# 609_motor.net
KiCad netlist of a schematic drawn in EAGLE
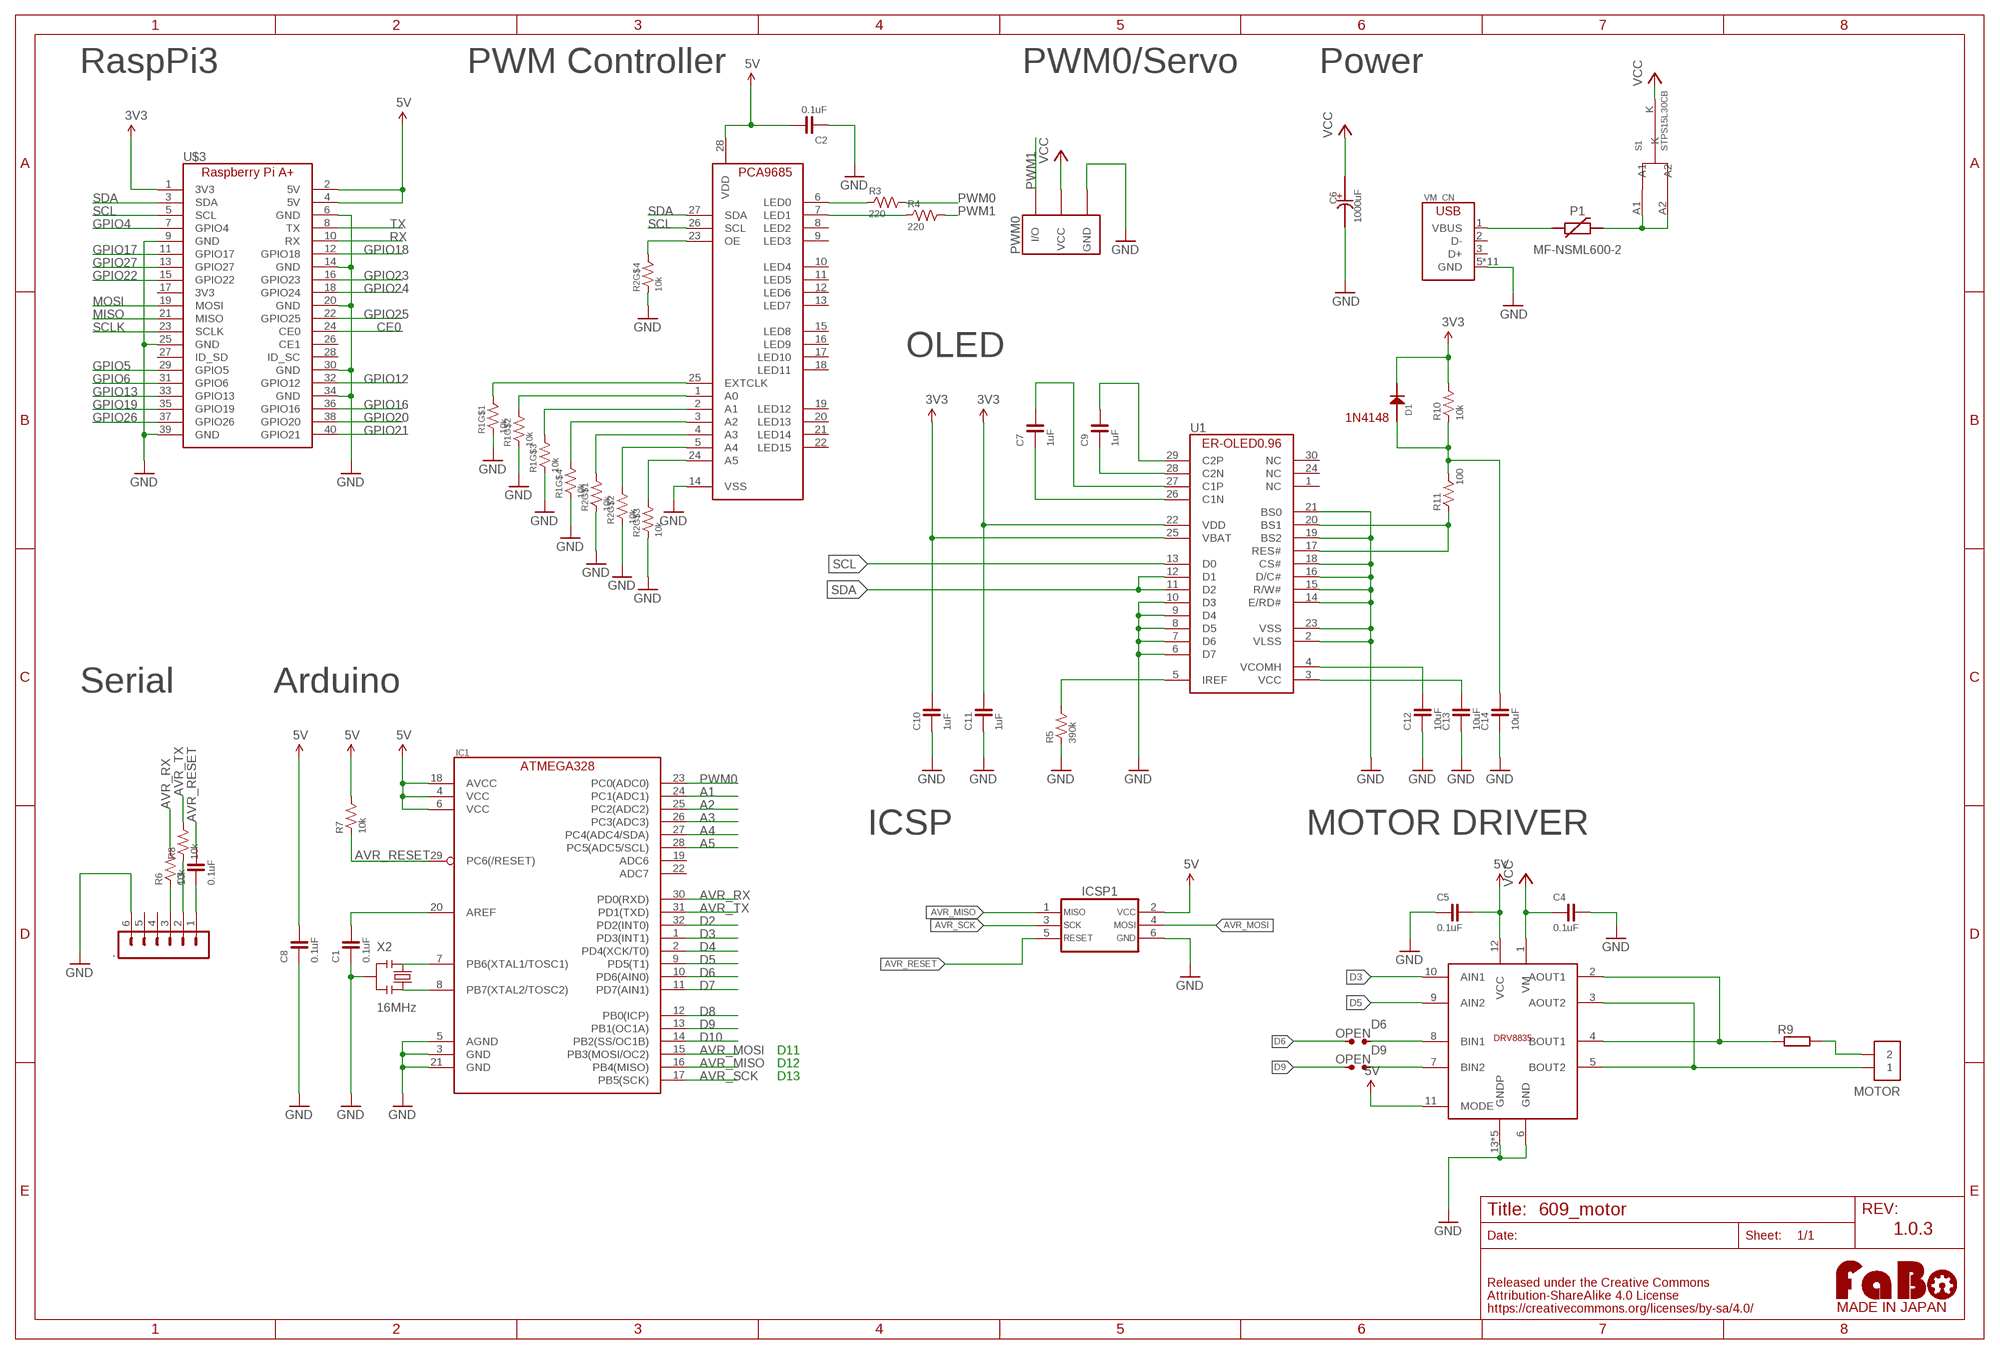
[diagram p0: schematic, sheet 1]

(export (version "E")
  (design (tool "Eeschema 10.0.6"))
  (components
    (comp (ref ".")
      (value "MA06-1")
      (footprint "eagle-import:MA06-1")
      (libsource (lib "eagle-import") (part "MA06-1"))
    )
    (comp (ref "C1")
      (value "0.1uF")
      (footprint "eagle-import:0603")
      (libsource (lib "eagle-import") (part "CAPACITOR-0603"))
    )
    (comp (ref "C2")
      (value "0.1uF")
      (footprint "eagle-import:0603")
      (libsource (lib "eagle-import") (part "CAPACITOR-0603"))
    )
    (comp (ref "C3")
      (value "0.1uF")
      (footprint "eagle-import:0603")
      (libsource (lib "eagle-import") (part "CAPACITOR-0603"))
    )
    (comp (ref "C4")
      (value "0.1uF")
      (footprint "eagle-import:0603")
      (libsource (lib "eagle-import") (part "CAPACITOR-0603"))
    )
    (comp (ref "C5")
      (value "0.1uF")
      (footprint "eagle-import:0603")
      (libsource (lib "eagle-import") (part "CAPACITOR-0603"))
    )
    (comp (ref "C6")
      (value "1000uF")
      (footprint "eagle-import:D12.5")
      (libsource (lib "eagle-import") (part "CAPACITOR-ALUMIN_D12_5"))
    )
    (comp (ref "C7")
      (value "1uF")
      (footprint "eagle-import:0603")
      (libsource (lib "eagle-import") (part "CAPACITOR-0603"))
    )
    (comp (ref "C8")
      (value "0.1uF")
      (footprint "eagle-import:0603")
      (libsource (lib "eagle-import") (part "CAPACITOR-0603"))
    )
    (comp (ref "C9")
      (value "1uF")
      (footprint "eagle-import:0603")
      (libsource (lib "eagle-import") (part "CAPACITOR-0603"))
    )
    (comp (ref "C10")
      (value "1uF")
      (footprint "eagle-import:0603")
      (libsource (lib "eagle-import") (part "CAPACITOR-0603"))
    )
    (comp (ref "C11")
      (value "1uF")
      (footprint "eagle-import:0603")
      (libsource (lib "eagle-import") (part "CAPACITOR-0603"))
    )
    (comp (ref "C12")
      (value "10uF")
      (footprint "eagle-import:0603")
      (libsource (lib "eagle-import") (part "CAPACITOR-0603"))
    )
    (comp (ref "C13")
      (value "10uF")
      (footprint "eagle-import:0603")
      (libsource (lib "eagle-import") (part "CAPACITOR-0603"))
    )
    (comp (ref "C14")
      (value "10uF")
      (footprint "eagle-import:0603")
      (libsource (lib "eagle-import") (part "CAPACITOR-0603"))
    )
    (comp (ref "D1")
      (value "1N4148")
      (footprint "eagle-import:1N4148W")
      (libsource (lib "eagle-import") (part "1N4148"))
    )
    (comp (ref "D6")
      (value "OPEN")
      (footprint "eagle-import:SMD-JUMPER-2-OPEN")
      (libsource (lib "eagle-import") (part "SMD-JUMPER-2-OPEN"))
    )
    (comp (ref "D9")
      (value "OPEN")
      (footprint "eagle-import:SMD-JUMPER-2-OPEN")
      (libsource (lib "eagle-import") (part "SMD-JUMPER-2-OPEN"))
    )
    (comp (ref "IC1")
      (value "ATMEGA328P-AU")
      (footprint "eagle-import:TQFP-32")
      (libsource (lib "eagle-import") (part "ATMEGA328P-AU"))
    )
    (comp (ref "ICSP1")
      (value "ICSP_AVR-TC_NOHOLE")
      (footprint "eagle-import:TC2030")
      (libsource (lib "eagle-import") (part "ICSP_AVR-TC_NOHOLE"))
    )
    (comp (ref "M1")
      (value "DRV8835")
      (footprint "eagle-import:DRV8835")
      (libsource (lib "eagle-import") (part "DRV8835"))
    )
    (comp (ref "MOTOR")
      (value "PIN_HEADER_1X2WIDE-WIDTH")
      (footprint "eagle-import:PIN_1X2_WIDE_WIDTH")
      (libsource (lib "eagle-import") (part "PIN_HEADER_1X2WIDE-WIDTH"))
    )
    (comp (ref "P1")
      (value "MF-NSML600-2")
      (footprint "eagle-import:1206")
      (libsource (lib "eagle-import") (part "POLYSWITCH1206"))
    )
    (comp (ref "PWM0")
      (value "FABO_BRICK_3PIN-HEADER")
      (footprint "eagle-import:FABO_BRICK_3PIN_HEADER")
      (libsource (lib "eagle-import") (part "FABO_BRICK_3PIN-HEADER"))
    )
    (comp (ref "R1")
      (value "10k")
      (footprint "eagle-import:EXBV8V")
      (libsource (lib "eagle-import") (part "RESISTOR_ARRAY"))
    )
    (comp (ref "R2")
      (value "10k")
      (footprint "eagle-import:EXBV8V")
      (libsource (lib "eagle-import") (part "RESISTOR_ARRAY"))
    )
    (comp (ref "R3")
      (value "220")
      (footprint "eagle-import:0603")
      (libsource (lib "eagle-import") (part "RESISTOR-0603"))
    )
    (comp (ref "R4")
      (value "220")
      (footprint "eagle-import:0603")
      (libsource (lib "eagle-import") (part "RESISTOR-0603"))
    )
    (comp (ref "R5")
      (value "390k")
      (footprint "eagle-import:0603")
      (libsource (lib "eagle-import") (part "RESISTOR-0603"))
    )
    (comp (ref "R6")
      (value "10k")
      (footprint "eagle-import:0603")
      (libsource (lib "eagle-import") (part "RESISTOR-0603"))
    )
    (comp (ref "R7")
      (value "10k")
      (footprint "eagle-import:0603")
      (libsource (lib "eagle-import") (part "RESISTOR-0603"))
    )
    (comp (ref "R8")
      (value "10k")
      (footprint "eagle-import:0603")
      (libsource (lib "eagle-import") (part "RESISTOR-0603"))
    )
    (comp (ref "R9")
      (value "R-EU_0922/22")
      (footprint "eagle-import:0922_22")
      (libsource (lib "eagle-import") (part "R-EU_0922/22"))
    )
    (comp (ref "R10")
      (value "10k")
      (footprint "eagle-import:0603")
      (libsource (lib "eagle-import") (part "RESISTOR-0603"))
    )
    (comp (ref "R11")
      (value "100")
      (footprint "eagle-import:0603")
      (libsource (lib "eagle-import") (part "RESISTOR-0603"))
    )
    (comp (ref "S1")
      (value "STPS15L30CB")
      (footprint "eagle-import:STPS15L30C")
      (libsource (lib "eagle-import") (part "STPS15L30C"))
    )
    (comp (ref "U$3")
      (value "RASPBERRY_PI_A+")
      (footprint "eagle-import:RASPBERRY_PI_A+")
      (libsource (lib "eagle-import") (part "RASPBERRY_PI_A+"))
    )
    (comp (ref "U$9")
      (value "PCA9685")
      (footprint "eagle-import:PCA9685")
      (libsource (lib "eagle-import") (part "PCA9685"))
    )
    (comp (ref "U$14")
      (value "LOGO_FABO-M")
      (footprint "eagle-import:LOGO_FABO_MS")
      (libsource (lib "eagle-import") (part "LOGO_FABO-M"))
    )
    (comp (ref "U1")
      (value "ER-OLED0.96-1ER-CON30HT-1")
      (footprint "eagle-import:ER-CON30HT-1")
      (libsource (lib "eagle-import") (part "ER-OLED0.96-1ER-CON30HT-1"))
    )
    (comp (ref "VM_CN")
      (value "USB-ZX62D")
      (footprint "eagle-import:ZX62D-B-5PA8")
      (libsource (lib "eagle-import") (part "USB-ZX62D"))
    )
    (comp (ref "X2")
      (value "16MHz")
      (footprint "eagle-import:CSTNE_V_C")
      (libsource (lib "eagle-import") (part "RESONATOR"))
    )
  )
  (nets
    (net (code "1") (name "/A1") (class "Default")
      (node (ref "IC1") (pin "24") (pinfunction "PC1(ADC1)_24") (pintype "bidirectional"))
    )
    (net (code "2") (name "/A2") (class "Default")
      (node (ref "IC1") (pin "25") (pinfunction "PC2(ADC2)_25") (pintype "bidirectional"))
    )
    (net (code "3") (name "/A3") (class "Default")
      (node (ref "IC1") (pin "26") (pinfunction "PC3(ADC3)_26") (pintype "bidirectional"))
    )
    (net (code "4") (name "/A4") (class "Default")
      (node (ref "IC1") (pin "27") (pinfunction "PC4(ADC4/SDA)_27") (pintype "bidirectional"))
    )
    (net (code "5") (name "/A5") (class "Default")
      (node (ref "IC1") (pin "28") (pinfunction "PC5(ADC5/SCL)_28") (pintype "bidirectional"))
    )
    (net (code "6") (name "/AVR_RX") (class "Default")
      (node (ref "IC1") (pin "30") (pinfunction "PD0(RXD)_30") (pintype "bidirectional"))
      (node (ref "R6") (pin "2") (pinfunction "2_2") (pintype "bidirectional"))
    )
    (net (code "7") (name "/AVR_TX") (class "Default")
      (node (ref "IC1") (pin "31") (pinfunction "PD1(TXD)_31") (pintype "bidirectional"))
      (node (ref "R8") (pin "2") (pinfunction "2_2") (pintype "bidirectional"))
    )
    (net (code "8") (name "/CE0") (class "Default")
      (node (ref "U$3") (pin "24") (pinfunction "CE0_24") (pintype "bidirectional"))
    )
    (net (code "9") (name "/D2") (class "Default")
      (node (ref "IC1") (pin "32") (pinfunction "PD2(INT0)_32") (pintype "bidirectional"))
    )
    (net (code "10") (name "/D4") (class "Default")
      (node (ref "IC1") (pin "2") (pinfunction "PD4(XCK/T0)_2") (pintype "bidirectional"))
    )
    (net (code "11") (name "/D7") (class "Default")
      (node (ref "IC1") (pin "11") (pinfunction "PD7(AIN1)_11") (pintype "bidirectional"))
    )
    (net (code "12") (name "/D8") (class "Default")
      (node (ref "IC1") (pin "12") (pinfunction "PB0(ICP)_12") (pintype "bidirectional"))
    )
    (net (code "13") (name "/D10") (class "Default")
      (node (ref "IC1") (pin "14") (pinfunction "PB2(SS/OC1B)_14") (pintype "bidirectional"))
    )
    (net (code "14") (name "/GPIO4") (class "Default")
      (node (ref "U$3") (pin "7") (pinfunction "GPIO4_7") (pintype "bidirectional"))
    )
    (net (code "15") (name "/GPIO5") (class "Default")
      (node (ref "U$3") (pin "29") (pinfunction "GPIO5_29") (pintype "bidirectional"))
    )
    (net (code "16") (name "/GPIO6") (class "Default")
      (node (ref "U$3") (pin "31") (pinfunction "GPIO6_31") (pintype "bidirectional"))
    )
    (net (code "17") (name "/GPIO12") (class "Default")
      (node (ref "U$3") (pin "32") (pinfunction "GPIO12_32") (pintype "bidirectional"))
    )
    (net (code "18") (name "/GPIO13") (class "Default")
      (node (ref "U$3") (pin "33") (pinfunction "GPIO13_33") (pintype "bidirectional"))
    )
    (net (code "19") (name "/GPIO16") (class "Default")
      (node (ref "U$3") (pin "36") (pinfunction "GPIO16_36") (pintype "bidirectional"))
    )
    (net (code "20") (name "/GPIO17") (class "Default")
      (node (ref "U$3") (pin "11") (pinfunction "GPIO17_11") (pintype "bidirectional"))
    )
    (net (code "21") (name "/GPIO18") (class "Default")
      (node (ref "U$3") (pin "12") (pinfunction "GPIO18_12") (pintype "bidirectional"))
    )
    (net (code "22") (name "/GPIO19") (class "Default")
      (node (ref "U$3") (pin "35") (pinfunction "GPIO19_35") (pintype "bidirectional"))
    )
    (net (code "23") (name "/GPIO20") (class "Default")
      (node (ref "U$3") (pin "38") (pinfunction "GPIO20_38") (pintype "bidirectional"))
    )
    (net (code "24") (name "/GPIO21") (class "Default")
      (node (ref "U$3") (pin "40") (pinfunction "GPIO21_40") (pintype "bidirectional"))
    )
    (net (code "25") (name "/GPIO22") (class "Default")
      (node (ref "U$3") (pin "15") (pinfunction "GPIO22_15") (pintype "bidirectional"))
    )
    (net (code "26") (name "/GPIO23") (class "Default")
      (node (ref "U$3") (pin "16") (pinfunction "GPIO23_16") (pintype "bidirectional"))
    )
    (net (code "27") (name "/GPIO24") (class "Default")
      (node (ref "U$3") (pin "18") (pinfunction "GPIO24_18") (pintype "bidirectional"))
    )
    (net (code "28") (name "/GPIO25") (class "Default")
      (node (ref "U$3") (pin "22") (pinfunction "GPIO25_22") (pintype "bidirectional"))
    )
    (net (code "29") (name "/GPIO26") (class "Default")
      (node (ref "U$3") (pin "37") (pinfunction "GPIO26_37") (pintype "bidirectional"))
    )
    (net (code "30") (name "/GPIO27") (class "Default")
      (node (ref "U$3") (pin "13") (pinfunction "GPIO27_13") (pintype "bidirectional"))
    )
    (net (code "31") (name "/MISO") (class "Default")
      (node (ref "U$3") (pin "21") (pinfunction "MISO_21") (pintype "bidirectional"))
    )
    (net (code "32") (name "/MOSI") (class "Default")
      (node (ref "U$3") (pin "19") (pinfunction "MOSI_19") (pintype "bidirectional"))
    )
    (net (code "33") (name "/PWM0") (class "Default")
      (node (ref "IC1") (pin "23") (pinfunction "PC0(ADC0)_23") (pintype "bidirectional"))
      (node (ref "R3") (pin "2") (pinfunction "2_2") (pintype "bidirectional"))
    )
    (net (code "34") (name "/PWM1") (class "Default")
      (node (ref "PWM0") (pin "I/O") (pinfunction "I/O_I/O") (pintype "bidirectional"))
      (node (ref "R4") (pin "2") (pinfunction "2_2") (pintype "bidirectional"))
    )
    (net (code "35") (name "/RX") (class "Default")
      (node (ref "U$3") (pin "10") (pinfunction "RX_10") (pintype "bidirectional"))
    )
    (net (code "36") (name "/SCLK") (class "Default")
      (node (ref "U$3") (pin "23") (pinfunction "SCLK_23") (pintype "bidirectional"))
    )
    (net (code "37") (name "/TX") (class "Default")
      (node (ref "U$3") (pin "8") (pinfunction "TX_8") (pintype "bidirectional"))
    )
    (net (code "38") (name "3V3") (class "Default")
      (node (ref "C10") (pin "2") (pinfunction "2_2") (pintype "passive"))
      (node (ref "C11") (pin "2") (pinfunction "2_2") (pintype "passive"))
      (node (ref "D1") (pin "CATHODE") (pinfunction "CATHODE_CATHODE") (pintype "bidirectional"))
      (node (ref "R10") (pin "2") (pinfunction "2_2") (pintype "bidirectional"))
      (node (ref "U$3") (pin "1") (pinfunction "3V3_1") (pintype "bidirectional"))
      (node (ref "U1") (pin "22") (pinfunction "VDD_22") (pintype "bidirectional"))
      (node (ref "U1") (pin "25") (pinfunction "VBAT_25") (pintype "bidirectional"))
    )
    (net (code "39") (name "5V") (class "Default")
      (node (ref "C2") (pin "2") (pinfunction "2_2") (pintype "passive"))
      (node (ref "C5") (pin "2") (pinfunction "2_2") (pintype "passive"))
      (node (ref "C8") (pin "2") (pinfunction "2_2") (pintype "passive"))
      (node (ref "IC1") (pin "18") (pinfunction "AVCC_18") (pintype "bidirectional"))
      (node (ref "IC1") (pin "4") (pinfunction "VCC_4") (pintype "bidirectional"))
      (node (ref "IC1") (pin "6") (pinfunction "VCC_6") (pintype "bidirectional"))
      (node (ref "ICSP1") (pin "2") (pinfunction "2_2") (pintype "passive"))
      (node (ref "M1") (pin "11") (pinfunction "MODE_11") (pintype "bidirectional"))
      (node (ref "M1") (pin "12") (pinfunction "VCC_12") (pintype "bidirectional"))
      (node (ref "R7") (pin "2") (pinfunction "2_2") (pintype "bidirectional"))
      (node (ref "U$3") (pin "2") (pinfunction "5V_2") (pintype "bidirectional"))
      (node (ref "U$3") (pin "4") (pinfunction "5V_4") (pintype "bidirectional"))
      (node (ref "U$9") (pin "28") (pinfunction "VDD_28") (pintype "bidirectional"))
    )
    (net (code "40") (name "AVR_MISO") (class "Default")
      (node (ref "IC1") (pin "16") (pinfunction "PB4(MISO)_16") (pintype "bidirectional"))
      (node (ref "ICSP1") (pin "1") (pinfunction "1_1") (pintype "passive"))
    )
    (net (code "41") (name "AVR_MOSI") (class "Default")
      (node (ref "IC1") (pin "15") (pinfunction "PB3(MOSI/OC2)_15") (pintype "bidirectional"))
      (node (ref "ICSP1") (pin "4") (pinfunction "4_4") (pintype "passive"))
    )
    (net (code "42") (name "AVR_RESET") (class "Default")
      (node (ref "C3") (pin "2") (pinfunction "2_2") (pintype "passive"))
      (node (ref "IC1") (pin "29") (pinfunction "PC6(/RESET)_29") (pintype "bidirectional"))
      (node (ref "ICSP1") (pin "5") (pinfunction "5_5") (pintype "passive"))
      (node (ref "R7") (pin "1") (pinfunction "1_1") (pintype "bidirectional"))
    )
    (net (code "43") (name "AVR_SCK") (class "Default")
      (node (ref "IC1") (pin "17") (pinfunction "PB5(SCK)_17") (pintype "bidirectional"))
      (node (ref "ICSP1") (pin "3") (pinfunction "3_3") (pintype "passive"))
    )
    (net (code "44") (name "D3") (class "Default")
      (node (ref "IC1") (pin "1") (pinfunction "PD3(INT1)_1") (pintype "bidirectional"))
      (node (ref "M1") (pin "10") (pinfunction "AIN1_10") (pintype "bidirectional"))
    )
    (net (code "45") (name "D5") (class "Default")
      (node (ref "IC1") (pin "9") (pinfunction "PD5(T1)_9") (pintype "bidirectional"))
      (node (ref "M1") (pin "9") (pinfunction "AIN2_9") (pintype "bidirectional"))
    )
    (net (code "46") (name "D6") (class "Default")
      (node (ref "D6") (pin "1") (pinfunction "1_1") (pintype "passive"))
      (node (ref "IC1") (pin "10") (pinfunction "PD6(AIN0)_10") (pintype "bidirectional"))
    )
    (net (code "47") (name "D9") (class "Default")
      (node (ref "D9") (pin "1") (pinfunction "1_1") (pintype "passive"))
      (node (ref "IC1") (pin "13") (pinfunction "PB1(OC1A)_13") (pintype "bidirectional"))
    )
    (net (code "48") (name "GND") (class "Default")
      (node (ref ".") (pin "6") (pinfunction "6_6") (pintype "passive"))
      (node (ref "C1") (pin "1") (pinfunction "1_1") (pintype "passive"))
      (node (ref "C10") (pin "1") (pinfunction "1_1") (pintype "passive"))
      (node (ref "C11") (pin "1") (pinfunction "1_1") (pintype "passive"))
      (node (ref "C12") (pin "1") (pinfunction "1_1") (pintype "passive"))
      (node (ref "C13") (pin "1") (pinfunction "1_1") (pintype "passive"))
      (node (ref "C14") (pin "1") (pinfunction "1_1") (pintype "passive"))
      (node (ref "C2") (pin "1") (pinfunction "1_1") (pintype "passive"))
      (node (ref "C4") (pin "2") (pinfunction "2_2") (pintype "passive"))
      (node (ref "C5") (pin "1") (pinfunction "1_1") (pintype "passive"))
      (node (ref "C6") (pin "-") (pinfunction "-_-") (pintype "passive"))
      (node (ref "C8") (pin "1") (pinfunction "1_1") (pintype "passive"))
      (node (ref "IC1") (pin "21") (pinfunction "GND_21") (pintype "bidirectional"))
      (node (ref "IC1") (pin "3") (pinfunction "GND_3") (pintype "bidirectional"))
      (node (ref "IC1") (pin "5") (pinfunction "AGND_5") (pintype "bidirectional"))
      (node (ref "ICSP1") (pin "6") (pinfunction "6_6") (pintype "passive"))
      (node (ref "M1") (pin "13") (pinfunction "GNDP_13") (pintype "bidirectional"))
      (node (ref "M1") (pin "14") (pinfunction "GNDP_14") (pintype "bidirectional"))
      (node (ref "M1") (pin "15") (pinfunction "GNDP_15") (pintype "bidirectional"))
      (node (ref "M1") (pin "16") (pinfunction "GNDP_16") (pintype "bidirectional"))
      (node (ref "M1") (pin "17") (pinfunction "GNDP_17") (pintype "bidirectional"))
      (node (ref "M1") (pin "6") (pinfunction "GND_6") (pintype "bidirectional"))
      (node (ref "PWM0") (pin "GND") (pinfunction "GND_GND") (pintype "bidirectional"))
      (node (ref "R1") (pin "1") (pinfunction "1_1") (pintype "bidirectional"))
      (node (ref "R1") (pin "2") (pinfunction "1_2") (pintype "bidirectional"))
      (node (ref "R1") (pin "3") (pinfunction "1_3") (pintype "bidirectional"))
      (node (ref "R1") (pin "4") (pinfunction "1_4") (pintype "bidirectional"))
      (node (ref "R2") (pin "1") (pinfunction "1_1") (pintype "bidirectional"))
      (node (ref "R2") (pin "2") (pinfunction "1_2") (pintype "bidirectional"))
      (node (ref "R2") (pin "3") (pinfunction "1_3") (pintype "bidirectional"))
      (node (ref "R2") (pin "4") (pinfunction "1_4") (pintype "bidirectional"))
      (node (ref "R5") (pin "1") (pinfunction "1_1") (pintype "bidirectional"))
      (node (ref "U$3") (pin "14") (pinfunction "GND_14") (pintype "bidirectional"))
      (node (ref "U$3") (pin "20") (pinfunction "GND_20") (pintype "bidirectional"))
      (node (ref "U$3") (pin "25") (pinfunction "GND_25") (pintype "bidirectional"))
      (node (ref "U$3") (pin "30") (pinfunction "GND_30") (pintype "bidirectional"))
      (node (ref "U$3") (pin "34") (pinfunction "GND_34") (pintype "bidirectional"))
      (node (ref "U$3") (pin "39") (pinfunction "GND_39") (pintype "bidirectional"))
      (node (ref "U$3") (pin "6") (pinfunction "GND_6") (pintype "bidirectional"))
      (node (ref "U$3") (pin "9") (pinfunction "GND_9") (pintype "bidirectional"))
      (node (ref "U$9") (pin "14") (pinfunction "VSS_14") (pintype "bidirectional"))
      (node (ref "U1") (pin "10") (pinfunction "D3_10") (pintype "bidirectional"))
      (node (ref "U1") (pin "14") (pinfunction "E/RD#_14") (pintype "bidirectional"))
      (node (ref "U1") (pin "15") (pinfunction "R/W#_15") (pintype "bidirectional"))
      (node (ref "U1") (pin "16") (pinfunction "D/C#_16") (pintype "bidirectional"))
      (node (ref "U1") (pin "18") (pinfunction "CS#_18") (pintype "bidirectional"))
      (node (ref "U1") (pin "19") (pinfunction "BS2_19") (pintype "bidirectional"))
      (node (ref "U1") (pin "2") (pinfunction "VLSS_2") (pintype "bidirectional"))
      (node (ref "U1") (pin "21") (pinfunction "BS0_21") (pintype "bidirectional"))
      (node (ref "U1") (pin "23") (pinfunction "VSS_23") (pintype "bidirectional"))
      (node (ref "U1") (pin "6") (pinfunction "D7_6") (pintype "bidirectional"))
      (node (ref "U1") (pin "7") (pinfunction "D6_7") (pintype "bidirectional"))
      (node (ref "U1") (pin "8") (pinfunction "D5_8") (pintype "bidirectional"))
      (node (ref "U1") (pin "9") (pinfunction "D4_9") (pintype "bidirectional"))
      (node (ref "VM_CN") (pin "5") (pinfunction "GND_5") (pintype "bidirectional"))
      (node (ref "VM_CN") (pin "B1") (pinfunction "GND_B1") (pintype "bidirectional"))
      (node (ref "VM_CN") (pin "B2") (pinfunction "GND_B2") (pintype "bidirectional"))
      (node (ref "VM_CN") (pin "B3") (pinfunction "GND_B3") (pintype "bidirectional"))
      (node (ref "VM_CN") (pin "B4") (pinfunction "GND_B4") (pintype "bidirectional"))
      (node (ref "VM_CN") (pin "T1") (pinfunction "GND_T1") (pintype "bidirectional"))
      (node (ref "VM_CN") (pin "T2") (pinfunction "GND_T2") (pintype "bidirectional"))
      (node (ref "VM_CN") (pin "T3") (pinfunction "GND_T3") (pintype "bidirectional"))
      (node (ref "VM_CN") (pin "T4") (pinfunction "GND_T4") (pintype "bidirectional"))
      (node (ref "VM_CN") (pin "T5") (pinfunction "GND_T5") (pintype "bidirectional"))
      (node (ref "VM_CN") (pin "T6") (pinfunction "GND_T6") (pintype "bidirectional"))
      (node (ref "X2") (pin "2") (pinfunction "2_2") (pintype "passive"))
    )
    (net (code "49") (name "Net-(.-Pad1)") (class "Default")
      (node (ref ".") (pin "1") (pinfunction "1_1") (pintype "passive"))
      (node (ref "C3") (pin "1") (pinfunction "1_1") (pintype "passive"))
    )
    (net (code "50") (name "Net-(.-Pad2)") (class "Default")
      (node (ref ".") (pin "2") (pinfunction "2_2") (pintype "passive"))
      (node (ref "R8") (pin "1") (pinfunction "1_1") (pintype "bidirectional"))
    )
    (net (code "51") (name "Net-(.-Pad3)") (class "Default")
      (node (ref ".") (pin "3") (pinfunction "3_3") (pintype "passive"))
      (node (ref "R6") (pin "1") (pinfunction "1_1") (pintype "bidirectional"))
    )
    (net (code "52") (name "Net-(C14-Pad2)") (class "Default")
      (node (ref "C14") (pin "2") (pinfunction "2_2") (pintype "passive"))
      (node (ref "D1") (pin "ANODE") (pinfunction "ANODE_ANODE") (pintype "bidirectional"))
      (node (ref "R10") (pin "1") (pinfunction "1_1") (pintype "bidirectional"))
      (node (ref "R11") (pin "2") (pinfunction "2_2") (pintype "bidirectional"))
    )
    (net (code "53") (name "Net-(IC1-AREF)") (class "Default")
      (node (ref "C1") (pin "2") (pinfunction "2_2") (pintype "passive"))
      (node (ref "IC1") (pin "20") (pinfunction "AREF_20") (pintype "bidirectional"))
    )
    (net (code "54") (name "Net-(IC1-PB6(XTAL1{slash}TOSC1))") (class "Default")
      (node (ref "IC1") (pin "7") (pinfunction "PB6(XTAL1/TOSC1)_7") (pintype "bidirectional"))
      (node (ref "X2") (pin "1") (pinfunction "1_1") (pintype "passive"))
    )
    (net (code "55") (name "Net-(IC1-PB7(XTAL2{slash}TOSC2))") (class "Default")
      (node (ref "IC1") (pin "8") (pinfunction "PB7(XTAL2/TOSC2)_8") (pintype "bidirectional"))
      (node (ref "X2") (pin "3") (pinfunction "3_3") (pintype "passive"))
    )
    (net (code "56") (name "Net-(M1-AOUT1)") (class "Default")
      (node (ref "M1") (pin "2") (pinfunction "AOUT1_2") (pintype "bidirectional"))
      (node (ref "M1") (pin "4") (pinfunction "BOUT1_4") (pintype "bidirectional"))
      (node (ref "R9") (pin "1") (pinfunction "1_1") (pintype "passive"))
    )
    (net (code "57") (name "Net-(M1-AOUT2)") (class "Default")
      (node (ref "M1") (pin "3") (pinfunction "AOUT2_3") (pintype "bidirectional"))
      (node (ref "M1") (pin "5") (pinfunction "BOUT2_5") (pintype "bidirectional"))
      (node (ref "MOTOR") (pin "1") (pinfunction "1_1") (pintype "bidirectional"))
    )
    (net (code "58") (name "Net-(M1-BIN1)") (class "Default")
      (node (ref "D6") (pin "2") (pinfunction "2_2") (pintype "passive"))
      (node (ref "M1") (pin "8") (pinfunction "BIN1_8") (pintype "bidirectional"))
    )
    (net (code "59") (name "Net-(M1-BIN2)") (class "Default")
      (node (ref "D9") (pin "2") (pinfunction "2_2") (pintype "passive"))
      (node (ref "M1") (pin "7") (pinfunction "BIN2_7") (pintype "bidirectional"))
    )
    (net (code "60") (name "Net-(MOTOR-Pad2)") (class "Default")
      (node (ref "MOTOR") (pin "2") (pinfunction "2_2") (pintype "bidirectional"))
      (node (ref "R9") (pin "2") (pinfunction "2_2") (pintype "passive"))
    )
    (net (code "61") (name "Net-(P1-1)") (class "Default")
      (node (ref "P1") (pin "P$1") (pinfunction "1_P$1") (pintype "bidirectional"))
      (node (ref "VM_CN") (pin "1") (pinfunction "VBUS_1") (pintype "bidirectional"))
    )
    (net (code "62") (name "Net-(P1-2)") (class "Default")
      (node (ref "P1") (pin "P$2") (pinfunction "2_P$2") (pintype "bidirectional"))
      (node (ref "S1") (pin "A1") (pinfunction "A1_A1") (pintype "bidirectional"))
      (node (ref "S1") (pin "A2") (pinfunction "A2_A2") (pintype "bidirectional"))
    )
    (net (code "63") (name "Net-(R1A-2)") (class "Default")
      (node (ref "R1") (pin "8") (pinfunction "2_8") (pintype "bidirectional"))
      (node (ref "U$9") (pin "25") (pinfunction "EXTCLK_25") (pintype "bidirectional"))
    )
    (net (code "64") (name "Net-(R1B-2)") (class "Default")
      (node (ref "R1") (pin "7") (pinfunction "2_7") (pintype "bidirectional"))
      (node (ref "U$9") (pin "1") (pinfunction "A0_1") (pintype "bidirectional"))
    )
    (net (code "65") (name "Net-(R1C-2)") (class "Default")
      (node (ref "R1") (pin "6") (pinfunction "2_6") (pintype "bidirectional"))
      (node (ref "U$9") (pin "2") (pinfunction "A1_2") (pintype "bidirectional"))
    )
    (net (code "66") (name "Net-(R1D-2)") (class "Default")
      (node (ref "R1") (pin "5") (pinfunction "2_5") (pintype "bidirectional"))
      (node (ref "U$9") (pin "3") (pinfunction "A2_3") (pintype "bidirectional"))
    )
    (net (code "67") (name "Net-(R2A-2)") (class "Default")
      (node (ref "R2") (pin "8") (pinfunction "2_8") (pintype "bidirectional"))
      (node (ref "U$9") (pin "4") (pinfunction "A3_4") (pintype "bidirectional"))
    )
    (net (code "68") (name "Net-(R2B-2)") (class "Default")
      (node (ref "R2") (pin "7") (pinfunction "2_7") (pintype "bidirectional"))
      (node (ref "U$9") (pin "5") (pinfunction "A4_5") (pintype "bidirectional"))
    )
    (net (code "69") (name "Net-(R2C-2)") (class "Default")
      (node (ref "R2") (pin "6") (pinfunction "2_6") (pintype "bidirectional"))
      (node (ref "U$9") (pin "24") (pinfunction "A5_24") (pintype "bidirectional"))
    )
    (net (code "70") (name "Net-(R2D-2)") (class "Default")
      (node (ref "R2") (pin "5") (pinfunction "2_5") (pintype "bidirectional"))
      (node (ref "U$9") (pin "23") (pinfunction "OE_23") (pintype "bidirectional"))
    )
    (net (code "71") (name "Net-(U$9-LED0)") (class "Default")
      (node (ref "R3") (pin "1") (pinfunction "1_1") (pintype "bidirectional"))
      (node (ref "U$9") (pin "6") (pinfunction "LED0_6") (pintype "bidirectional"))
    )
    (net (code "72") (name "Net-(U$9-LED1)") (class "Default")
      (node (ref "R4") (pin "1") (pinfunction "1_1") (pintype "bidirectional"))
      (node (ref "U$9") (pin "7") (pinfunction "LED1_7") (pintype "bidirectional"))
    )
    (net (code "73") (name "Net-(U1-BS1)") (class "Default")
      (node (ref "R11") (pin "1") (pinfunction "1_1") (pintype "bidirectional"))
      (node (ref "U1") (pin "17") (pinfunction "RES#_17") (pintype "bidirectional"))
      (node (ref "U1") (pin "20") (pinfunction "BS1_20") (pintype "bidirectional"))
    )
    (net (code "74") (name "Net-(U1-C1N)") (class "Default")
      (node (ref "C7") (pin "1") (pinfunction "1_1") (pintype "passive"))
      (node (ref "U1") (pin "26") (pinfunction "C1N_26") (pintype "bidirectional"))
    )
    (net (code "75") (name "Net-(U1-C1P)") (class "Default")
      (node (ref "C7") (pin "2") (pinfunction "2_2") (pintype "passive"))
      (node (ref "U1") (pin "27") (pinfunction "C1P_27") (pintype "bidirectional"))
    )
    (net (code "76") (name "Net-(U1-C2N)") (class "Default")
      (node (ref "C9") (pin "1") (pinfunction "1_1") (pintype "passive"))
      (node (ref "U1") (pin "28") (pinfunction "C2N_28") (pintype "bidirectional"))
    )
    (net (code "77") (name "Net-(U1-C2P)") (class "Default")
      (node (ref "C9") (pin "2") (pinfunction "2_2") (pintype "passive"))
      (node (ref "U1") (pin "29") (pinfunction "C2P_29") (pintype "bidirectional"))
    )
    (net (code "78") (name "Net-(U1-IREF)") (class "Default")
      (node (ref "R5") (pin "2") (pinfunction "2_2") (pintype "bidirectional"))
      (node (ref "U1") (pin "5") (pinfunction "IREF_5") (pintype "bidirectional"))
    )
    (net (code "79") (name "Net-(U1-VCC)") (class "Default")
      (node (ref "C13") (pin "2") (pinfunction "2_2") (pintype "passive"))
      (node (ref "U1") (pin "3") (pinfunction "VCC_3") (pintype "bidirectional"))
    )
    (net (code "80") (name "Net-(U1-VCOMH)") (class "Default")
      (node (ref "C12") (pin "2") (pinfunction "2_2") (pintype "passive"))
      (node (ref "U1") (pin "4") (pinfunction "VCOMH_4") (pintype "bidirectional"))
    )
    (net (code "81") (name "SCL") (class "Default")
      (node (ref "U$3") (pin "5") (pinfunction "SCL_5") (pintype "bidirectional"))
      (node (ref "U$9") (pin "26") (pinfunction "SCL_26") (pintype "bidirectional"))
      (node (ref "U1") (pin "13") (pinfunction "D0_13") (pintype "bidirectional"))
    )
    (net (code "82") (name "SDA") (class "Default")
      (node (ref "U$3") (pin "3") (pinfunction "SDA_3") (pintype "bidirectional"))
      (node (ref "U$9") (pin "27") (pinfunction "SDA_27") (pintype "bidirectional"))
      (node (ref "U1") (pin "11") (pinfunction "D2_11") (pintype "bidirectional"))
      (node (ref "U1") (pin "12") (pinfunction "D1_12") (pintype "bidirectional"))
    )
    (net (code "83") (name "VCC") (class "Default")
      (node (ref "C4") (pin "1") (pinfunction "1_1") (pintype "passive"))
      (node (ref "C6") (pin "+") (pinfunction "+_+") (pintype "passive"))
      (node (ref "M1") (pin "1") (pinfunction "VM_1") (pintype "bidirectional"))
      (node (ref "PWM0") (pin "VCC") (pinfunction "VCC_VCC") (pintype "bidirectional"))
      (node (ref "S1") (pin "K") (pinfunction "K_K") (pintype "bidirectional"))
    )
    (net (code "84") (name "unconnected-(.-Pad4)") (class "Default")
      (node (ref ".") (pin "4") (pinfunction "4_4") (pintype "passive"))
    )
    (net (code "85") (name "unconnected-(.-Pad5)") (class "Default")
      (node (ref ".") (pin "5") (pinfunction "5_5") (pintype "passive"))
    )
    (net (code "86") (name "unconnected-(IC1-ADC6-Pad19)") (class "Default")
      (node (ref "IC1") (pin "19") (pinfunction "ADC6_19") (pintype "bidirectional"))
    )
    (net (code "87") (name "unconnected-(IC1-ADC7-Pad22)") (class "Default")
      (node (ref "IC1") (pin "22") (pinfunction "ADC7_22") (pintype "bidirectional"))
    )
    (net (code "88") (name "unconnected-(U$3-3V3-Pad17)") (class "Default")
      (node (ref "U$3") (pin "17") (pinfunction "3V3_17") (pintype "bidirectional"))
    )
    (net (code "89") (name "unconnected-(U$3-CE1-Pad26)") (class "Default")
      (node (ref "U$3") (pin "26") (pinfunction "CE1_26") (pintype "bidirectional"))
    )
    (net (code "90") (name "unconnected-(U$3-ID_SC-Pad28)") (class "Default")
      (node (ref "U$3") (pin "28") (pinfunction "ID_SC_28") (pintype "bidirectional"))
    )
    (net (code "91") (name "unconnected-(U$3-ID_SD-Pad27)") (class "Default")
      (node (ref "U$3") (pin "27") (pinfunction "ID_SD_27") (pintype "bidirectional"))
    )
    (net (code "92") (name "unconnected-(U$9-LED2-Pad8)") (class "Default")
      (node (ref "U$9") (pin "8") (pinfunction "LED2_8") (pintype "bidirectional"))
    )
    (net (code "93") (name "unconnected-(U$9-LED3-Pad9)") (class "Default")
      (node (ref "U$9") (pin "9") (pinfunction "LED3_9") (pintype "bidirectional"))
    )
    (net (code "94") (name "unconnected-(U$9-LED4-Pad10)") (class "Default")
      (node (ref "U$9") (pin "10") (pinfunction "LED4_10") (pintype "bidirectional"))
    )
    (net (code "95") (name "unconnected-(U$9-LED5-Pad11)") (class "Default")
      (node (ref "U$9") (pin "11") (pinfunction "LED5_11") (pintype "bidirectional"))
    )
    (net (code "96") (name "unconnected-(U$9-LED6-Pad12)") (class "Default")
      (node (ref "U$9") (pin "12") (pinfunction "LED6_12") (pintype "bidirectional"))
    )
    (net (code "97") (name "unconnected-(U$9-LED7-Pad13)") (class "Default")
      (node (ref "U$9") (pin "13") (pinfunction "LED7_13") (pintype "bidirectional"))
    )
    (net (code "98") (name "unconnected-(U$9-LED8-Pad15)") (class "Default")
      (node (ref "U$9") (pin "15") (pinfunction "LED8_15") (pintype "bidirectional"))
    )
    (net (code "99") (name "unconnected-(U$9-LED9-Pad16)") (class "Default")
      (node (ref "U$9") (pin "16") (pinfunction "LED9_16") (pintype "bidirectional"))
    )
    (net (code "100") (name "unconnected-(U$9-LED10-Pad17)") (class "Default")
      (node (ref "U$9") (pin "17") (pinfunction "LED10_17") (pintype "bidirectional"))
    )
    (net (code "101") (name "unconnected-(U$9-LED11-Pad18)") (class "Default")
      (node (ref "U$9") (pin "18") (pinfunction "LED11_18") (pintype "bidirectional"))
    )
    (net (code "102") (name "unconnected-(U$9-LED12-Pad19)") (class "Default")
      (node (ref "U$9") (pin "19") (pinfunction "LED12_19") (pintype "bidirectional"))
    )
    (net (code "103") (name "unconnected-(U$9-LED13-Pad20)") (class "Default")
      (node (ref "U$9") (pin "20") (pinfunction "LED13_20") (pintype "bidirectional"))
    )
    (net (code "104") (name "unconnected-(U$9-LED14-Pad21)") (class "Default")
      (node (ref "U$9") (pin "21") (pinfunction "LED14_21") (pintype "bidirectional"))
    )
    (net (code "105") (name "unconnected-(U$9-LED15-Pad22)") (class "Default")
      (node (ref "U$9") (pin "22") (pinfunction "LED15_22") (pintype "bidirectional"))
    )
    (net (code "106") (name "unconnected-(U1-NC-Pad1)") (class "Default")
      (node (ref "U1") (pin "1") (pinfunction "NC_1") (pintype "bidirectional"))
    )
    (net (code "107") (name "unconnected-(U1-NC-Pad24)") (class "Default")
      (node (ref "U1") (pin "24") (pinfunction "NC_24") (pintype "bidirectional"))
    )
    (net (code "108") (name "unconnected-(U1-NC-Pad30)") (class "Default")
      (node (ref "U1") (pin "30") (pinfunction "NC_30") (pintype "bidirectional"))
    )
    (net (code "109") (name "unconnected-(VM_CN-D+-Pad3)") (class "Default")
      (node (ref "VM_CN") (pin "3") (pinfunction "D+_3") (pintype "bidirectional"))
    )
    (net (code "110") (name "unconnected-(VM_CN-D--Pad2)") (class "Default")
      (node (ref "VM_CN") (pin "2") (pinfunction "D-_2") (pintype "bidirectional"))
    )
  )
)
